# 1-WireCounter.net
KiCad netlist of a schematic drawn in EAGLE
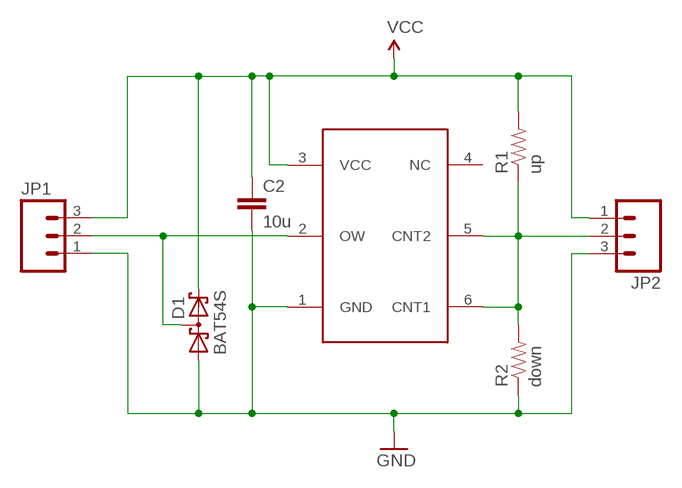
[diagram p0: schematic, sheet 1]

(export (version "E")
  (design (tool "Eeschema 10.0.6"))
  (components
    (comp (ref "C2")
      (value "10u")
      (footprint "eagle-import:0603-CAP")
      (libsource (lib "eagle-import") (part "CAP0603-CAP"))
    )
    (comp (ref "D1")
      (value "BAT54S")
      (footprint "eagle-import:SOT23")
      (libsource (lib "eagle-import") (part "BAT54S"))
    )
    (comp (ref "JP1")
      (value "M03LOCK")
      (footprint "eagle-import:1X03_LOCK")
      (libsource (lib "eagle-import") (part "M03LOCK"))
    )
    (comp (ref "JP2")
      (value "M03LOCK")
      (footprint "eagle-import:1X03_LOCK")
      (libsource (lib "eagle-import") (part "M03LOCK"))
    )
    (comp (ref "R1")
      (value "up")
      (footprint "eagle-import:0603-RES")
      (libsource (lib "eagle-import") (part "RESISTOR0603-RES"))
    )
    (comp (ref "R2")
      (value "down")
      (footprint "eagle-import:0603-RES")
      (libsource (lib "eagle-import") (part "RESISTOR0603-RES"))
    )
    (comp (ref "U$2")
      (value "DS2423P")
      (footprint "eagle-import:TSOC6")
      (libsource (lib "eagle-import") (part "DS2423P"))
    )
  )
  (nets
    (net (code "1") (name "GND") (class "Default")
      (node (ref "C2") (pin "2") (pinfunction "2_2") (pintype "passive"))
      (node (ref "D1") (pin "1") (pinfunction "A1_1") (pintype "passive"))
      (node (ref "JP1") (pin "1") (pinfunction "1_1") (pintype "passive"))
      (node (ref "JP2") (pin "3") (pinfunction "3_3") (pintype "passive"))
      (node (ref "R2") (pin "1") (pinfunction "1_1") (pintype "passive"))
      (node (ref "U$2") (pin "1") (pinfunction "GND_1") (pintype "bidirectional"))
    )
    (net (code "2") (name "Net-(D1-C1A2)") (class "Default")
      (node (ref "D1") (pin "3") (pinfunction "C1A2_3") (pintype "passive"))
      (node (ref "JP1") (pin "2") (pinfunction "2_2") (pintype "passive"))
      (node (ref "U$2") (pin "2") (pinfunction "OW_2") (pintype "bidirectional"))
    )
    (net (code "3") (name "Net-(U$2-CNT1)") (class "Default")
      (node (ref "JP2") (pin "2") (pinfunction "2_2") (pintype "passive"))
      (node (ref "R1") (pin "1") (pinfunction "1_1") (pintype "passive"))
      (node (ref "R2") (pin "2") (pinfunction "2_2") (pintype "passive"))
      (node (ref "U$2") (pin "5") (pinfunction "CNT2_5") (pintype "bidirectional"))
      (node (ref "U$2") (pin "6") (pinfunction "CNT1_6") (pintype "bidirectional"))
    )
    (net (code "4") (name "VCC") (class "Default")
      (node (ref "C2") (pin "1") (pinfunction "1_1") (pintype "passive"))
      (node (ref "D1") (pin "2") (pinfunction "C2_2") (pintype "passive"))
      (node (ref "JP1") (pin "3") (pinfunction "3_3") (pintype "passive"))
      (node (ref "JP2") (pin "1") (pinfunction "1_1") (pintype "passive"))
      (node (ref "R1") (pin "2") (pinfunction "2_2") (pintype "passive"))
      (node (ref "U$2") (pin "3") (pinfunction "VCC_3") (pintype "bidirectional"))
    )
    (net (code "5") (name "unconnected-(U$2-NC-Pad4)") (class "Default")
      (node (ref "U$2") (pin "4") (pinfunction "NC_4") (pintype "bidirectional"))
    )
  )
)
